# StampOfApproval.net
KiCad netlist of a schematic drawn in EAGLE
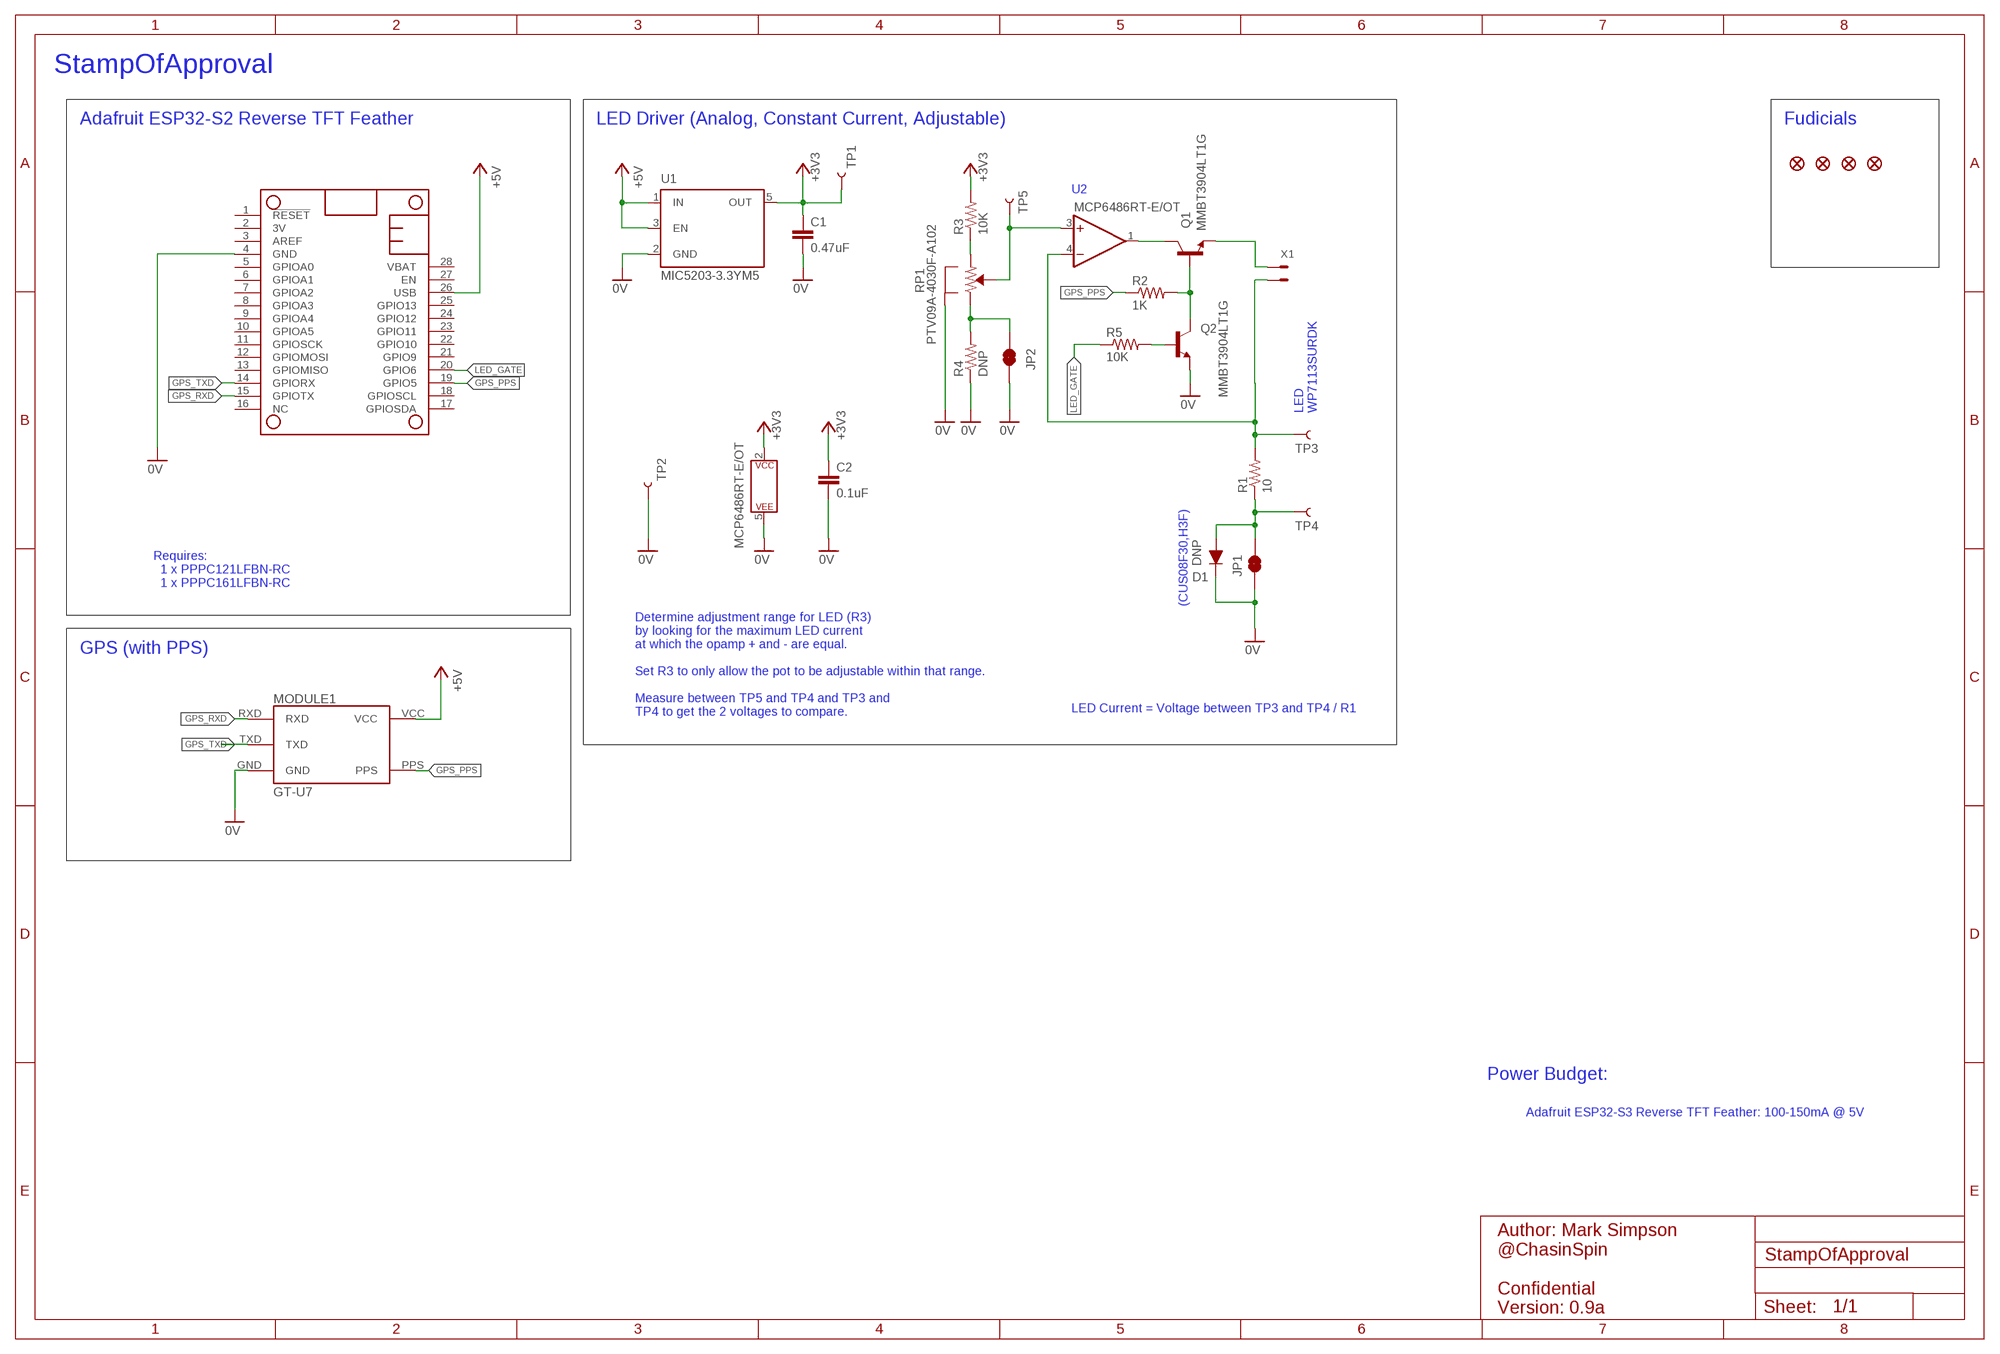
[diagram p0: schematic, sheet 1]

(export (version "E")
  (design (tool "Eeschema 10.0.6"))
  (components
    (comp (ref "C1")
      (value "0.47uF")
      (footprint "eagle-import:C0603K")
      (libsource (lib "eagle-import") (part "C-EU"))
    )
    (comp (ref "C2")
      (value "0.1uF")
      (footprint "eagle-import:C0603K")
      (libsource (lib "eagle-import") (part "C-EU"))
    )
    (comp (ref "D1")
      (value "DNP")
      (footprint "eagle-import:CUS08F30")
      (libsource (lib "eagle-import") (part "CUS08F30"))
    )
    (comp (ref "FD1")
      (value "FIDUCIALUFIDUCIAL")
      (footprint "eagle-import:FIDUCIAL-MICRO")
      (libsource (lib "eagle-import") (part "FIDUCIALUFIDUCIAL"))
    )
    (comp (ref "FD2")
      (value "FIDUCIALUFIDUCIAL")
      (footprint "eagle-import:FIDUCIAL-MICRO")
      (libsource (lib "eagle-import") (part "FIDUCIALUFIDUCIAL"))
    )
    (comp (ref "FD3")
      (value "FIDUCIALUFIDUCIAL")
      (footprint "eagle-import:FIDUCIAL-MICRO")
      (libsource (lib "eagle-import") (part "FIDUCIALUFIDUCIAL"))
    )
    (comp (ref "FD4")
      (value "FIDUCIALUFIDUCIAL")
      (footprint "eagle-import:FIDUCIAL-MICRO")
      (libsource (lib "eagle-import") (part "FIDUCIALUFIDUCIAL"))
    )
    (comp (ref "JP1")
      (value "JUMPER-SMT_2_NC_TRACE")
      (footprint "eagle-import:SMT-JUMPER_2_NC_TRACE_SILK-WIDEPOWER")
      (libsource (lib "eagle-import") (part "JUMPER-SMT_2_NC_TRACE"))
    )
    (comp (ref "JP2")
      (value "JUMPER-SMT_2_NC_TRACE")
      (footprint "eagle-import:SMT-JUMPER_2_NC_TRACE_SILK-WIDEPOWER")
      (libsource (lib "eagle-import") (part "JUMPER-SMT_2_NC_TRACE"))
    )
    (comp (ref "MODULE1")
      (value "GT-U7")
      (footprint "eagle-import:GT-U7")
      (libsource (lib "eagle-import") (part "GT-U7"))
    )
    (comp (ref "MS1")
      (value "FEATHERWING_NODIM")
      (footprint "eagle-import:FEATHERWING_DIM")
      (libsource (lib "eagle-import") (part "FEATHERWING_NODIM"))
    )
    (comp (ref "Q1")
      (value "MMBT3904LT1G")
      (footprint "eagle-import:SOT23-BEC")
      (libsource (lib "eagle-import") (part "MMBT3904LT1G"))
    )
    (comp (ref "Q2")
      (value "MMBT3904LT1G")
      (footprint "eagle-import:SOT23-BEC")
      (libsource (lib "eagle-import") (part "MMBT3904LT1G"))
    )
    (comp (ref "R1")
      (value "10")
      (footprint "eagle-import:R0603")
      (libsource (lib "eagle-import") (part "R-US_R0603"))
    )
    (comp (ref "R2")
      (value "1K")
      (footprint "eagle-import:R0603")
      (libsource (lib "eagle-import") (part "R-US_R0603"))
    )
    (comp (ref "R3")
      (value "10K")
      (footprint "eagle-import:R0603")
      (libsource (lib "eagle-import") (part "R-US_R0603"))
    )
    (comp (ref "R4")
      (value "DNP")
      (footprint "eagle-import:R0603")
      (libsource (lib "eagle-import") (part "R-US_R0603"))
    )
    (comp (ref "R5")
      (value "10K")
      (footprint "eagle-import:R0603")
      (libsource (lib "eagle-import") (part "R-US_R0603"))
    )
    (comp (ref "RP1")
      (value "PTV09A-4030F-A102")
      (footprint "eagle-import:PTV09A-4")
      (libsource (lib "eagle-import") (part "PTV09A-4"))
    )
    (comp (ref "TP1")
      (value "TEST-POINT3")
      (footprint "eagle-import:PAD.03X.03")
      (libsource (lib "eagle-import") (part "TEST-POINT3"))
    )
    (comp (ref "TP2")
      (value "TEST-POINT3")
      (footprint "eagle-import:PAD.03X.03")
      (libsource (lib "eagle-import") (part "TEST-POINT3"))
    )
    (comp (ref "TP3")
      (value "TEST-POINT3")
      (footprint "eagle-import:PAD.03X.03")
      (libsource (lib "eagle-import") (part "TEST-POINT3"))
    )
    (comp (ref "TP4")
      (value "TEST-POINT3")
      (footprint "eagle-import:PAD.03X.03")
      (libsource (lib "eagle-import") (part "TEST-POINT3"))
    )
    (comp (ref "TP5")
      (value "TEST-POINT3")
      (footprint "eagle-import:PAD.03X.03")
      (libsource (lib "eagle-import") (part "TEST-POINT3"))
    )
    (comp (ref "U1")
      (value "MIC5203-3.3YM5")
      (footprint "eagle-import:SOT23-5")
      (libsource (lib "eagle-import") (part "MIC5203-3.3YM5"))
    )
    (comp (ref "U2")
      (value "MCP6486RT-E/OT")
      (footprint "eagle-import:SOT23-5")
      (libsource (lib "eagle-import") (part "LMV641"))
    )
    (comp (ref "X1")
      (value "SOLDER_CONTACTS")
      (footprint "eagle-import:SOLDER_CONTACTS")
      (libsource (lib "eagle-import") (part "SOLDER_CONTACTS"))
    )
  )
  (nets
    (net (code "1") (name "+3V3") (class "Default")
      (node (ref "C1") (pin "1") (pinfunction "1_1") (pintype "passive"))
      (node (ref "C2") (pin "1") (pinfunction "1_1") (pintype "passive"))
      (node (ref "R3") (pin "2") (pinfunction "2_2") (pintype "passive"))
      (node (ref "TP1") (pin "P$1") (pinfunction "1_P$1") (pintype "bidirectional"))
      (node (ref "U1") (pin "5") (pinfunction "OUT_5") (pintype "power_in"))
      (node (ref "U2") (pin "2") (pinfunction "P$V+_2") (pintype "bidirectional"))
    )
    (net (code "2") (name "+5V") (class "Default")
      (node (ref "MODULE1") (pin "VCC") (pinfunction "VCC_VCC") (pintype "power_in"))
      (node (ref "MS1") (pin "26") (pinfunction "USB_26") (pintype "power_in"))
      (node (ref "U1") (pin "1") (pinfunction "IN_1") (pintype "power_in"))
      (node (ref "U1") (pin "3") (pinfunction "EN_3") (pintype "input"))
    )
    (net (code "3") (name "/3V") (class "Default")
      (node (ref "MS1") (pin "2") (pinfunction "3V_2") (pintype "power_in"))
    )
    (net (code "4") (name "/VBAT") (class "Default")
      (node (ref "MS1") (pin "28") (pinfunction "VBAT_28") (pintype "power_in"))
    )
    (net (code "5") (name "0V") (class "Default")
      (node (ref "C1") (pin "2") (pinfunction "2_2") (pintype "passive"))
      (node (ref "C2") (pin "2") (pinfunction "2_2") (pintype "passive"))
      (node (ref "D1") (pin "K") (pinfunction "K_K") (pintype "passive"))
      (node (ref "JP1") (pin "1") (pinfunction "1_1") (pintype "passive"))
      (node (ref "JP2") (pin "1") (pinfunction "1_1") (pintype "passive"))
      (node (ref "MODULE1") (pin "GND") (pinfunction "GND_GND") (pintype "power_in"))
      (node (ref "MS1") (pin "4") (pinfunction "GND_4") (pintype "power_in"))
      (node (ref "Q2") (pin "E") (pinfunction "E_E") (pintype "passive"))
      (node (ref "R4") (pin "1") (pinfunction "1_1") (pintype "passive"))
      (node (ref "RP1") (pin "SHIELD1") (pinfunction "SHIELD_SHIELD1") (pintype "passive"))
      (node (ref "RP1") (pin "SHIELD2") (pinfunction "SHIELD_SHIELD2") (pintype "passive"))
      (node (ref "TP2") (pin "P$1") (pinfunction "1_P$1") (pintype "bidirectional"))
      (node (ref "U1") (pin "2") (pinfunction "GND_2") (pintype "power_in"))
      (node (ref "U2") (pin "5") (pinfunction "P$V-_5") (pintype "bidirectional"))
    )
    (net (code "6") (name "GPS_PPS") (class "Default")
      (node (ref "MODULE1") (pin "PPS") (pinfunction "PPS_PPS") (pintype "output"))
      (node (ref "MS1") (pin "19") (pinfunction "GPIO5_19") (pintype "bidirectional"))
      (node (ref "R2") (pin "1") (pinfunction "1_1") (pintype "passive"))
    )
    (net (code "7") (name "GPS_RXD") (class "Default")
      (node (ref "MODULE1") (pin "RXD") (pinfunction "RXD_RXD") (pintype "input"))
      (node (ref "MS1") (pin "15") (pinfunction "GPIOTX_15") (pintype "bidirectional"))
    )
    (net (code "8") (name "GPS_TXD") (class "Default")
      (node (ref "MODULE1") (pin "TXD") (pinfunction "TXD_TXD") (pintype "output"))
      (node (ref "MS1") (pin "14") (pinfunction "GPIORX_14") (pintype "bidirectional"))
    )
    (net (code "9") (name "LED_GATE") (class "Default")
      (node (ref "MS1") (pin "20") (pinfunction "GPIO6_20") (pintype "bidirectional"))
      (node (ref "R5") (pin "1") (pinfunction "1_1") (pintype "passive"))
    )
    (net (code "10") (name "Net-(Q1-PadB)") (class "Default")
      (node (ref "Q1") (pin "B") (pinfunction "B_B") (pintype "passive"))
      (node (ref "Q2") (pin "C") (pinfunction "C_C") (pintype "passive"))
      (node (ref "R2") (pin "2") (pinfunction "2_2") (pintype "passive"))
    )
    (net (code "11") (name "Net-(Q1-PadE)") (class "Default")
      (node (ref "Q1") (pin "E") (pinfunction "E_E") (pintype "passive"))
      (node (ref "X1") (pin "1") (pinfunction "1_1") (pintype "passive"))
    )
    (net (code "12") (name "Net-(Q2-PadB)") (class "Default")
      (node (ref "Q2") (pin "B") (pinfunction "B_B") (pintype "passive"))
      (node (ref "R5") (pin "2") (pinfunction "2_2") (pintype "passive"))
    )
    (net (code "13") (name "Net-(RP1-CCW)") (class "Default")
      (node (ref "R3") (pin "1") (pinfunction "1_1") (pintype "passive"))
      (node (ref "RP1") (pin "3") (pinfunction "CCW_3") (pintype "passive"))
    )
    (net (code "14") (name "Net-(RP1-CW)") (class "Default")
      (node (ref "JP2") (pin "2") (pinfunction "2_2") (pintype "passive"))
      (node (ref "R4") (pin "2") (pinfunction "2_2") (pintype "passive"))
      (node (ref "RP1") (pin "1") (pinfunction "CW_1") (pintype "passive"))
    )
    (net (code "15") (name "Net-(RP1-WIPER)") (class "Default")
      (node (ref "RP1") (pin "2") (pinfunction "WIPER_2") (pintype "passive"))
      (node (ref "TP5") (pin "P$1") (pinfunction "1_P$1") (pintype "bidirectional"))
      (node (ref "U2") (pin "3") (pinfunction "+IN_3") (pintype "input"))
    )
    (net (code "16") (name "Net-(TP3-1)") (class "Default")
      (node (ref "R1") (pin "2") (pinfunction "2_2") (pintype "passive"))
      (node (ref "TP3") (pin "P$1") (pinfunction "1_P$1") (pintype "bidirectional"))
      (node (ref "U2") (pin "4") (pinfunction "-IN_4") (pintype "input"))
      (node (ref "X1") (pin "2") (pinfunction "2_2") (pintype "passive"))
    )
    (net (code "17") (name "Net-(TP4-1)") (class "Default")
      (node (ref "D1") (pin "A") (pinfunction "A_A") (pintype "passive"))
      (node (ref "JP1") (pin "2") (pinfunction "2_2") (pintype "passive"))
      (node (ref "R1") (pin "1") (pinfunction "1_1") (pintype "passive"))
      (node (ref "TP4") (pin "P$1") (pinfunction "1_P$1") (pintype "bidirectional"))
    )
    (net (code "18") (name "Net-(U2A-OUT)") (class "Default")
      (node (ref "Q1") (pin "C") (pinfunction "C_C") (pintype "passive"))
      (node (ref "U2") (pin "1") (pinfunction "OUT_1") (pintype "output"))
    )
    (net (code "19") (name "unconnected-(MS1-AREF-Pad3)") (class "Default")
      (node (ref "MS1") (pin "3") (pinfunction "AREF_3") (pintype "passive"))
    )
    (net (code "20") (name "unconnected-(MS1-EN-Pad27)") (class "Default")
      (node (ref "MS1") (pin "27") (pinfunction "EN_27") (pintype "passive"))
    )
    (net (code "21") (name "unconnected-(MS1-GPIO9-Pad21)") (class "Default")
      (node (ref "MS1") (pin "21") (pinfunction "GPIO9_21") (pintype "bidirectional"))
    )
    (net (code "22") (name "unconnected-(MS1-GPIO10-Pad22)") (class "Default")
      (node (ref "MS1") (pin "22") (pinfunction "GPIO10_22") (pintype "bidirectional"))
    )
    (net (code "23") (name "unconnected-(MS1-GPIO11-Pad23)") (class "Default")
      (node (ref "MS1") (pin "23") (pinfunction "GPIO11_23") (pintype "bidirectional"))
    )
    (net (code "24") (name "unconnected-(MS1-GPIO12-Pad24)") (class "Default")
      (node (ref "MS1") (pin "24") (pinfunction "GPIO12_24") (pintype "bidirectional"))
    )
    (net (code "25") (name "unconnected-(MS1-GPIO13-Pad25)") (class "Default")
      (node (ref "MS1") (pin "25") (pinfunction "GPIO13_25") (pintype "bidirectional"))
    )
    (net (code "26") (name "unconnected-(MS1-GPIOA0-Pad5)") (class "Default")
      (node (ref "MS1") (pin "5") (pinfunction "GPIOA0_5") (pintype "bidirectional"))
    )
    (net (code "27") (name "unconnected-(MS1-GPIOA1-Pad6)") (class "Default")
      (node (ref "MS1") (pin "6") (pinfunction "GPIOA1_6") (pintype "bidirectional"))
    )
    (net (code "28") (name "unconnected-(MS1-GPIOA2-Pad7)") (class "Default")
      (node (ref "MS1") (pin "7") (pinfunction "GPIOA2_7") (pintype "bidirectional"))
    )
    (net (code "29") (name "unconnected-(MS1-GPIOA3-Pad8)") (class "Default")
      (node (ref "MS1") (pin "8") (pinfunction "GPIOA3_8") (pintype "bidirectional"))
    )
    (net (code "30") (name "unconnected-(MS1-GPIOA4-Pad9)") (class "Default")
      (node (ref "MS1") (pin "9") (pinfunction "GPIOA4_9") (pintype "bidirectional"))
    )
    (net (code "31") (name "unconnected-(MS1-GPIOA5-Pad10)") (class "Default")
      (node (ref "MS1") (pin "10") (pinfunction "GPIOA5_10") (pintype "bidirectional"))
    )
    (net (code "32") (name "unconnected-(MS1-GPIOMISO-Pad13)") (class "Default")
      (node (ref "MS1") (pin "13") (pinfunction "GPIOMISO_13") (pintype "bidirectional"))
    )
    (net (code "33") (name "unconnected-(MS1-GPIOMOSI-Pad12)") (class "Default")
      (node (ref "MS1") (pin "12") (pinfunction "GPIOMOSI_12") (pintype "bidirectional"))
    )
    (net (code "34") (name "unconnected-(MS1-GPIOSCK-Pad11)") (class "Default")
      (node (ref "MS1") (pin "11") (pinfunction "GPIOSCK_11") (pintype "bidirectional"))
    )
    (net (code "35") (name "unconnected-(MS1-GPIOSCL-Pad18)") (class "Default")
      (node (ref "MS1") (pin "18") (pinfunction "GPIOSCL_18") (pintype "bidirectional"))
    )
    (net (code "36") (name "unconnected-(MS1-GPIOSDA-Pad17)") (class "Default")
      (node (ref "MS1") (pin "17") (pinfunction "GPIOSDA_17") (pintype "bidirectional"))
    )
    (net (code "37") (name "unconnected-(MS1-NC-Pad16)") (class "Default")
      (node (ref "MS1") (pin "16") (pinfunction "NC_16") (pintype "passive"))
    )
    (net (code "38") (name "unconnected-(MS1-~{RESET}-Pad1)") (class "Default")
      (node (ref "MS1") (pin "1") (pinfunction "~{RESET}_1") (pintype "input"))
    )
  )
)
